# Thermostat.net
KiCad netlist of a schematic drawn in EAGLE
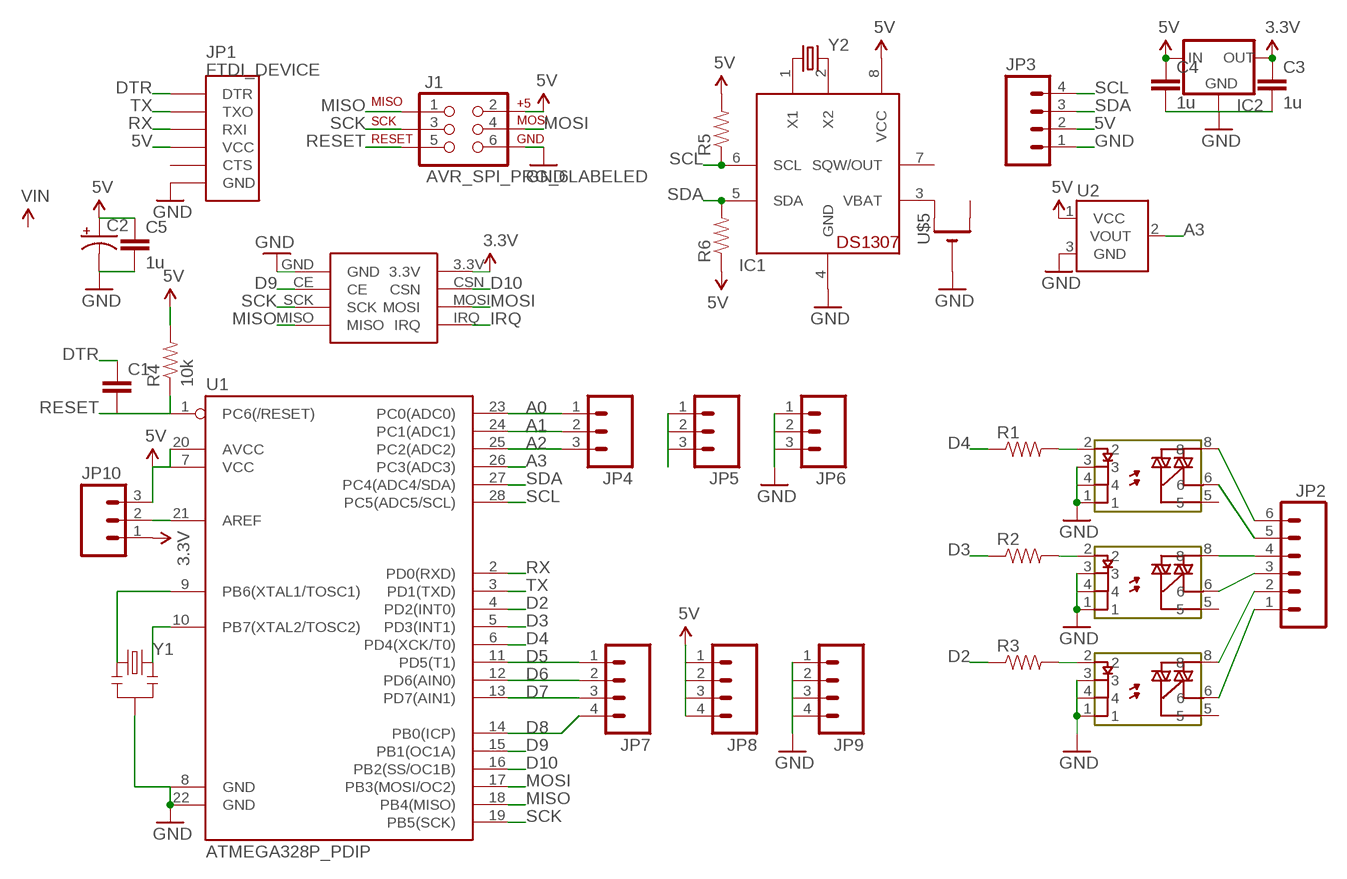
[diagram p0: schematic, sheet 1]

(export (version "E")
  (design (tool "Eeschema 10.0.6"))
  (components
    (comp (ref "C1")
      (value "CAPPTH")
      (footprint "eagle-import:CAP-PTH-SMALL")
      (libsource (lib "eagle-import") (part "CAPPTH"))
    )
    (comp (ref "C2")
      (value "CAP_POLPTH1")
      (footprint "eagle-import:CPOL-RADIAL-100UF-25V")
      (libsource (lib "eagle-import") (part "CAP_POLPTH1"))
    )
    (comp (ref "C3")
      (value "1u")
      (footprint "eagle-import:CAP-PTH-SMALL")
      (libsource (lib "eagle-import") (part "CAPPTH"))
    )
    (comp (ref "C4")
      (value "1u")
      (footprint "eagle-import:CAP-PTH-SMALL")
      (libsource (lib "eagle-import") (part "CAPPTH"))
    )
    (comp (ref "C5")
      (value "1u")
      (footprint "eagle-import:CAP-PTH-SMALL")
      (libsource (lib "eagle-import") (part "CAPPTH"))
    )
    (comp (ref "IC1")
      (value "DS1307")
      (footprint "eagle-import:DIL08")
      (libsource (lib "eagle-import") (part "DS1307"))
    )
    (comp (ref "IC2")
      (value "MCP1700INLINE")
      (footprint "eagle-import:TO92-INLINE")
      (libsource (lib "eagle-import") (part "MCP1700INLINE"))
    )
    (comp (ref "J1")
      (value "AVR_SPI_PRG_6LABELED")
      (footprint "eagle-import:2X3-NS")
      (libsource (lib "eagle-import") (part "AVR_SPI_PRG_6LABELED"))
    )
    (comp (ref "JP1")
      (value "FTDI_DEVICE")
      (footprint "eagle-import:FTDI_DEVICE_SIDE")
      (libsource (lib "eagle-import") (part "FTDI_DEVICE"))
    )
    (comp (ref "JP2")
      (value "M063.5MM-6")
      (footprint "eagle-import:SCREWTERMINAL-3.5MM-6")
      (libsource (lib "eagle-import") (part "M063.5MM-6"))
    )
    (comp (ref "JP3")
      (value "M04PTH")
      (footprint "eagle-import:1X04")
      (libsource (lib "eagle-import") (part "M04PTH"))
    )
    (comp (ref "JP4")
      (value "M03PTH")
      (footprint "eagle-import:1X03")
      (libsource (lib "eagle-import") (part "M03PTH"))
    )
    (comp (ref "JP5")
      (value "M03PTH")
      (footprint "eagle-import:1X03")
      (libsource (lib "eagle-import") (part "M03PTH"))
    )
    (comp (ref "JP6")
      (value "M03PTH")
      (footprint "eagle-import:1X03")
      (libsource (lib "eagle-import") (part "M03PTH"))
    )
    (comp (ref "JP7")
      (value "M04PTH")
      (footprint "eagle-import:1X04")
      (libsource (lib "eagle-import") (part "M04PTH"))
    )
    (comp (ref "JP8")
      (value "M04PTH")
      (footprint "eagle-import:1X04")
      (libsource (lib "eagle-import") (part "M04PTH"))
    )
    (comp (ref "JP9")
      (value "M04PTH")
      (footprint "eagle-import:1X04")
      (libsource (lib "eagle-import") (part "M04PTH"))
    )
    (comp (ref "JP10")
      (value "M03PTH")
      (footprint "eagle-import:1X03")
      (libsource (lib "eagle-import") (part "M03PTH"))
    )
    (comp (ref "R1")
      (value "RESISTORAXIAL-0.3")
      (footprint "eagle-import:AXIAL-0.3")
      (libsource (lib "eagle-import") (part "RESISTORAXIAL-0.3"))
    )
    (comp (ref "R2")
      (value "RESISTORAXIAL-0.3")
      (footprint "eagle-import:AXIAL-0.3")
      (libsource (lib "eagle-import") (part "RESISTORAXIAL-0.3"))
    )
    (comp (ref "R3")
      (value "RESISTORAXIAL-0.3")
      (footprint "eagle-import:AXIAL-0.3")
      (libsource (lib "eagle-import") (part "RESISTORAXIAL-0.3"))
    )
    (comp (ref "R4")
      (value "10k")
      (footprint "eagle-import:AXIAL-0.3")
      (libsource (lib "eagle-import") (part "RESISTORAXIAL-0.3"))
    )
    (comp (ref "R5")
      (value "RESISTORAXIAL-0.3")
      (footprint "eagle-import:AXIAL-0.3")
      (libsource (lib "eagle-import") (part "RESISTORAXIAL-0.3"))
    )
    (comp (ref "R6")
      (value "RESISTORAXIAL-0.3")
      (footprint "eagle-import:AXIAL-0.3")
      (libsource (lib "eagle-import") (part "RESISTORAXIAL-0.3"))
    )
    (comp (ref "U$1")
      (value "PR39MF5")
      (footprint "eagle-import:PR39MF51")
      (libsource (lib "eagle-import") (part "PR39MF5"))
    )
    (comp (ref "U$2")
      (value "PR39MF5")
      (footprint "eagle-import:PR39MF51")
      (libsource (lib "eagle-import") (part "PR39MF5"))
    )
    (comp (ref "U$3")
      (value "PR39MF5")
      (footprint "eagle-import:PR39MF51")
      (libsource (lib "eagle-import") (part "PR39MF5"))
    )
    (comp (ref "U$4")
      (value "RF24_MODULE")
      (footprint "eagle-import:RF24_SOCKET")
      (libsource (lib "eagle-import") (part "RF24_MODULE"))
    )
    (comp (ref "U$5")
      (value "CR1220THM")
      (footprint "eagle-import:CR1220-THM")
      (libsource (lib "eagle-import") (part "CR1220THM"))
    )
    (comp (ref "U1")
      (value "ATMEGA328P_PDIP")
      (footprint "eagle-import:DIL28-3")
      (libsource (lib "eagle-import") (part "ATMEGA328P_PDIP"))
    )
    (comp (ref "U2")
      (value "TMP36GT9")
      (footprint "eagle-import:TO-92")
      (libsource (lib "eagle-import") (part "TMP36GT9"))
    )
    (comp (ref "Y1")
      (value "RESONATORPTH")
      (footprint "eagle-import:RESONATOR-PTH")
      (libsource (lib "eagle-import") (part "RESONATORPTH"))
    )
    (comp (ref "Y2")
      (value "CRYSTALTC26H")
      (footprint "eagle-import:TC26H")
      (libsource (lib "eagle-import") (part "CRYSTALTC26H"))
    )
  )
  (nets
    (net (code "1") (name "/A0") (class "Default")
      (node (ref "JP4") (pin "1") (pinfunction "1_1") (pintype "passive"))
      (node (ref "U1") (pin "23") (pinfunction "PC0(ADC0)_23") (pintype "bidirectional"))
    )
    (net (code "2") (name "/A1") (class "Default")
      (node (ref "JP4") (pin "2") (pinfunction "2_2") (pintype "passive"))
      (node (ref "U1") (pin "24") (pinfunction "PC1(ADC1)_24") (pintype "bidirectional"))
    )
    (net (code "3") (name "/A2") (class "Default")
      (node (ref "JP4") (pin "3") (pinfunction "3_3") (pintype "passive"))
      (node (ref "U1") (pin "25") (pinfunction "PC2(ADC2)_25") (pintype "bidirectional"))
    )
    (net (code "4") (name "/A3") (class "Default")
      (node (ref "U1") (pin "26") (pinfunction "PC3(ADC3)_26") (pintype "bidirectional"))
      (node (ref "U2") (pin "2") (pinfunction "VOUT_2") (pintype "bidirectional"))
    )
    (net (code "5") (name "/AREF") (class "Default")
      (node (ref "JP10") (pin "2") (pinfunction "2_2") (pintype "passive"))
      (node (ref "JP5") (pin "1") (pinfunction "1_1") (pintype "passive"))
      (node (ref "JP5") (pin "2") (pinfunction "2_2") (pintype "passive"))
      (node (ref "JP5") (pin "3") (pinfunction "3_3") (pintype "passive"))
      (node (ref "U1") (pin "21") (pinfunction "AREF_21") (pintype "bidirectional"))
    )
    (net (code "6") (name "/D2") (class "Default")
      (node (ref "R3") (pin "P$1") (pinfunction "1_P$1") (pintype "passive"))
      (node (ref "U1") (pin "4") (pinfunction "PD2(INT0)_4") (pintype "bidirectional"))
    )
    (net (code "7") (name "/D3") (class "Default")
      (node (ref "R2") (pin "P$1") (pinfunction "1_P$1") (pintype "passive"))
      (node (ref "U1") (pin "5") (pinfunction "PD3(INT1)_5") (pintype "bidirectional"))
    )
    (net (code "8") (name "/D4") (class "Default")
      (node (ref "R1") (pin "P$1") (pinfunction "1_P$1") (pintype "passive"))
      (node (ref "U1") (pin "6") (pinfunction "PD4(XCK/T0)_6") (pintype "bidirectional"))
    )
    (net (code "9") (name "/D5") (class "Default")
      (node (ref "JP7") (pin "1") (pinfunction "1_1") (pintype "passive"))
      (node (ref "U1") (pin "11") (pinfunction "PD5(T1)_11") (pintype "bidirectional"))
    )
    (net (code "10") (name "/D6") (class "Default")
      (node (ref "JP7") (pin "2") (pinfunction "2_2") (pintype "passive"))
      (node (ref "U1") (pin "12") (pinfunction "PD6(AIN0)_12") (pintype "bidirectional"))
    )
    (net (code "11") (name "/D7") (class "Default")
      (node (ref "JP7") (pin "3") (pinfunction "3_3") (pintype "passive"))
      (node (ref "U1") (pin "13") (pinfunction "PD7(AIN1)_13") (pintype "bidirectional"))
    )
    (net (code "12") (name "/D8") (class "Default")
      (node (ref "JP7") (pin "4") (pinfunction "4_4") (pintype "passive"))
      (node (ref "U1") (pin "14") (pinfunction "PB0(ICP)_14") (pintype "bidirectional"))
    )
    (net (code "13") (name "/D9") (class "Default")
      (node (ref "U$4") (pin "CE") (pinfunction "CE_CE") (pintype "bidirectional"))
      (node (ref "U1") (pin "15") (pinfunction "PB1(OC1A)_15") (pintype "bidirectional"))
    )
    (net (code "14") (name "/D10") (class "Default")
      (node (ref "U$4") (pin "CSN") (pinfunction "CSN_CSN") (pintype "bidirectional"))
      (node (ref "U1") (pin "16") (pinfunction "PB2(SS/OC1B)_16") (pintype "bidirectional"))
    )
    (net (code "15") (name "/DTR") (class "Default")
      (node (ref "C1") (pin "1") (pinfunction "1_1") (pintype "passive"))
      (node (ref "JP1") (pin "P$1") (pinfunction "DTR_P$1") (pintype "bidirectional"))
    )
    (net (code "16") (name "/IRQ") (class "Default")
      (node (ref "U$4") (pin "IRQ") (pinfunction "IRQ_IRQ") (pintype "bidirectional"))
    )
    (net (code "17") (name "/MISO") (class "Default")
      (node (ref "J1") (pin "1") (pinfunction "1_1") (pintype "passive"))
      (node (ref "U$4") (pin "MISO") (pinfunction "MISO_MISO") (pintype "bidirectional"))
      (node (ref "U1") (pin "18") (pinfunction "PB4(MISO)_18") (pintype "bidirectional"))
    )
    (net (code "18") (name "/MOSI") (class "Default")
      (node (ref "J1") (pin "4") (pinfunction "4_4") (pintype "passive"))
      (node (ref "U$4") (pin "MOSI") (pinfunction "MOSI_MOSI") (pintype "bidirectional"))
      (node (ref "U1") (pin "17") (pinfunction "PB3(MOSI/OC2)_17") (pintype "bidirectional"))
    )
    (net (code "19") (name "/RESET") (class "Default")
      (node (ref "C1") (pin "2") (pinfunction "2_2") (pintype "passive"))
      (node (ref "J1") (pin "5") (pinfunction "5_5") (pintype "passive"))
      (node (ref "R4") (pin "P$1") (pinfunction "1_P$1") (pintype "passive"))
      (node (ref "U1") (pin "1") (pinfunction "PC6(/RESET)_1") (pintype "bidirectional"))
    )
    (net (code "20") (name "/RX") (class "Default")
      (node (ref "JP1") (pin "P$3") (pinfunction "RXI_P$3") (pintype "bidirectional"))
      (node (ref "U1") (pin "2") (pinfunction "PD0(RXD)_2") (pintype "bidirectional"))
    )
    (net (code "21") (name "/SCK") (class "Default")
      (node (ref "J1") (pin "3") (pinfunction "3_3") (pintype "passive"))
      (node (ref "U$4") (pin "SCK") (pinfunction "SCK_SCK") (pintype "bidirectional"))
      (node (ref "U1") (pin "19") (pinfunction "PB5(SCK)_19") (pintype "bidirectional"))
    )
    (net (code "22") (name "/SCL") (class "Default")
      (node (ref "IC1") (pin "6") (pinfunction "SCL_6") (pintype "bidirectional"))
      (node (ref "JP3") (pin "4") (pinfunction "4_4") (pintype "passive"))
      (node (ref "R5") (pin "P$1") (pinfunction "1_P$1") (pintype "passive"))
      (node (ref "U1") (pin "28") (pinfunction "PC5(ADC5/SCL)_28") (pintype "bidirectional"))
    )
    (net (code "23") (name "/SDA") (class "Default")
      (node (ref "IC1") (pin "5") (pinfunction "SDA_5") (pintype "bidirectional"))
      (node (ref "JP3") (pin "3") (pinfunction "3_3") (pintype "passive"))
      (node (ref "R6") (pin "P$2") (pinfunction "2_P$2") (pintype "passive"))
      (node (ref "U1") (pin "27") (pinfunction "PC4(ADC4/SDA)_27") (pintype "bidirectional"))
    )
    (net (code "24") (name "/TX") (class "Default")
      (node (ref "JP1") (pin "P$2") (pinfunction "TXO_P$2") (pintype "bidirectional"))
      (node (ref "U1") (pin "3") (pinfunction "PD1(TXD)_3") (pintype "bidirectional"))
    )
    (net (code "25") (name "3.3V") (class "Default")
      (node (ref "C3") (pin "1") (pinfunction "1_1") (pintype "passive"))
      (node (ref "IC2") (pin "3") (pinfunction "OUT_3") (pintype "passive"))
      (node (ref "JP10") (pin "1") (pinfunction "1_1") (pintype "passive"))
      (node (ref "U$4") (pin "3.3V") (pinfunction "3.3V_3.3V") (pintype "bidirectional"))
    )
    (net (code "26") (name "5V") (class "Default")
      (node (ref "C2") (pin "1") (pinfunction "+_1") (pintype "passive"))
      (node (ref "C4") (pin "1") (pinfunction "1_1") (pintype "passive"))
      (node (ref "C5") (pin "1") (pinfunction "1_1") (pintype "passive"))
      (node (ref "IC1") (pin "8") (pinfunction "VCC_8") (pintype "power_in"))
      (node (ref "IC2") (pin "2") (pinfunction "IN_2") (pintype "input"))
      (node (ref "J1") (pin "2") (pinfunction "2_2") (pintype "passive"))
      (node (ref "JP1") (pin "P$4") (pinfunction "VCC_P$4") (pintype "bidirectional"))
      (node (ref "JP10") (pin "3") (pinfunction "3_3") (pintype "passive"))
      (node (ref "JP3") (pin "2") (pinfunction "2_2") (pintype "passive"))
      (node (ref "JP8") (pin "1") (pinfunction "1_1") (pintype "passive"))
      (node (ref "JP8") (pin "2") (pinfunction "2_2") (pintype "passive"))
      (node (ref "JP8") (pin "3") (pinfunction "3_3") (pintype "passive"))
      (node (ref "JP8") (pin "4") (pinfunction "4_4") (pintype "passive"))
      (node (ref "R4") (pin "P$2") (pinfunction "2_P$2") (pintype "passive"))
      (node (ref "R5") (pin "P$2") (pinfunction "2_P$2") (pintype "passive"))
      (node (ref "R6") (pin "P$1") (pinfunction "1_P$1") (pintype "passive"))
      (node (ref "U1") (pin "20") (pinfunction "AVCC_20") (pintype "bidirectional"))
      (node (ref "U1") (pin "7") (pinfunction "VCC_7") (pintype "bidirectional"))
      (node (ref "U2") (pin "1") (pinfunction "VCC_1") (pintype "bidirectional"))
    )
    (net (code "27") (name "GND") (class "Default")
      (node (ref "C2") (pin "2") (pinfunction "-_2") (pintype "passive"))
      (node (ref "C3") (pin "2") (pinfunction "2_2") (pintype "passive"))
      (node (ref "C4") (pin "2") (pinfunction "2_2") (pintype "passive"))
      (node (ref "C5") (pin "2") (pinfunction "2_2") (pintype "passive"))
      (node (ref "IC1") (pin "4") (pinfunction "GND_4") (pintype "power_in"))
      (node (ref "IC2") (pin "1") (pinfunction "GND_1") (pintype "input"))
      (node (ref "J1") (pin "6") (pinfunction "6_6") (pintype "passive"))
      (node (ref "JP1") (pin "P$6") (pinfunction "GND_P$6") (pintype "bidirectional"))
      (node (ref "JP3") (pin "1") (pinfunction "1_1") (pintype "passive"))
      (node (ref "JP6") (pin "1") (pinfunction "1_1") (pintype "passive"))
      (node (ref "JP6") (pin "2") (pinfunction "2_2") (pintype "passive"))
      (node (ref "JP6") (pin "3") (pinfunction "3_3") (pintype "passive"))
      (node (ref "JP9") (pin "1") (pinfunction "1_1") (pintype "passive"))
      (node (ref "JP9") (pin "2") (pinfunction "2_2") (pintype "passive"))
      (node (ref "JP9") (pin "3") (pinfunction "3_3") (pintype "passive"))
      (node (ref "JP9") (pin "4") (pinfunction "4_4") (pintype "passive"))
      (node (ref "U$1") (pin "1") (pinfunction "1_1") (pintype "input"))
      (node (ref "U$1") (pin "3") (pinfunction "3_3") (pintype "input"))
      (node (ref "U$1") (pin "4") (pinfunction "4_4") (pintype "input"))
      (node (ref "U$2") (pin "1") (pinfunction "1_1") (pintype "input"))
      (node (ref "U$2") (pin "3") (pinfunction "3_3") (pintype "input"))
      (node (ref "U$2") (pin "4") (pinfunction "4_4") (pintype "input"))
      (node (ref "U$3") (pin "1") (pinfunction "1_1") (pintype "input"))
      (node (ref "U$3") (pin "3") (pinfunction "3_3") (pintype "input"))
      (node (ref "U$3") (pin "4") (pinfunction "4_4") (pintype "input"))
      (node (ref "U$4") (pin "GND") (pinfunction "GND_GND") (pintype "bidirectional"))
      (node (ref "U$5") (pin "-") (pinfunction "-_-") (pintype "passive"))
      (node (ref "U1") (pin "22") (pinfunction "GND_22") (pintype "bidirectional"))
      (node (ref "U1") (pin "8") (pinfunction "GND_8") (pintype "bidirectional"))
      (node (ref "U2") (pin "3") (pinfunction "GND_3") (pintype "bidirectional"))
      (node (ref "Y1") (pin "2") (pinfunction "2_2") (pintype "passive"))
    )
    (net (code "28") (name "Net-(IC1-VBAT)") (class "Default")
      (node (ref "IC1") (pin "3") (pinfunction "VBAT_3") (pintype "power_in"))
      (node (ref "U$5") (pin "+1") (pinfunction "+_+1") (pintype "passive"))
    )
    (net (code "29") (name "Net-(IC1-X1)") (class "Default")
      (node (ref "IC1") (pin "1") (pinfunction "X1_1") (pintype "passive"))
      (node (ref "Y2") (pin "1") (pinfunction "1_1") (pintype "passive"))
    )
    (net (code "30") (name "Net-(IC1-X2)") (class "Default")
      (node (ref "IC1") (pin "2") (pinfunction "X2_2") (pintype "passive"))
      (node (ref "Y2") (pin "2") (pinfunction "2_2") (pintype "passive"))
    )
    (net (code "31") (name "Net-(JP2-Pad1)") (class "Default")
      (node (ref "JP2") (pin "1") (pinfunction "1_1") (pintype "passive"))
      (node (ref "U$3") (pin "6") (pinfunction "6_6") (pintype "output"))
    )
    (net (code "32") (name "Net-(JP2-Pad2)") (class "Default")
      (node (ref "JP2") (pin "2") (pinfunction "2_2") (pintype "passive"))
      (node (ref "U$3") (pin "8") (pinfunction "8_8") (pintype "output"))
    )
    (net (code "33") (name "Net-(JP2-Pad3)") (class "Default")
      (node (ref "JP2") (pin "3") (pinfunction "3_3") (pintype "passive"))
      (node (ref "U$2") (pin "6") (pinfunction "6_6") (pintype "output"))
    )
    (net (code "34") (name "Net-(JP2-Pad4)") (class "Default")
      (node (ref "JP2") (pin "4") (pinfunction "4_4") (pintype "passive"))
      (node (ref "U$2") (pin "8") (pinfunction "8_8") (pintype "output"))
    )
    (net (code "35") (name "Net-(JP2-Pad5)") (class "Default")
      (node (ref "JP2") (pin "5") (pinfunction "5_5") (pintype "passive"))
      (node (ref "U$1") (pin "6") (pinfunction "6_6") (pintype "output"))
    )
    (net (code "36") (name "Net-(JP2-Pad6)") (class "Default")
      (node (ref "JP2") (pin "6") (pinfunction "6_6") (pintype "passive"))
      (node (ref "U$1") (pin "8") (pinfunction "8_8") (pintype "output"))
    )
    (net (code "37") (name "Net-(R1-2)") (class "Default")
      (node (ref "R1") (pin "P$2") (pinfunction "2_P$2") (pintype "passive"))
      (node (ref "U$1") (pin "2") (pinfunction "2_2") (pintype "input"))
    )
    (net (code "38") (name "Net-(R2-2)") (class "Default")
      (node (ref "R2") (pin "P$2") (pinfunction "2_P$2") (pintype "passive"))
      (node (ref "U$2") (pin "2") (pinfunction "2_2") (pintype "input"))
    )
    (net (code "39") (name "Net-(R3-2)") (class "Default")
      (node (ref "R3") (pin "P$2") (pinfunction "2_P$2") (pintype "passive"))
      (node (ref "U$3") (pin "2") (pinfunction "2_2") (pintype "input"))
    )
    (net (code "40") (name "Net-(U1-PB6(XTAL1{slash}TOSC1))") (class "Default")
      (node (ref "U1") (pin "9") (pinfunction "PB6(XTAL1/TOSC1)_9") (pintype "bidirectional"))
      (node (ref "Y1") (pin "1") (pinfunction "1_1") (pintype "passive"))
    )
    (net (code "41") (name "Net-(U1-PB7(XTAL2{slash}TOSC2))") (class "Default")
      (node (ref "U1") (pin "10") (pinfunction "PB7(XTAL2/TOSC2)_10") (pintype "bidirectional"))
      (node (ref "Y1") (pin "3") (pinfunction "3_3") (pintype "passive"))
    )
    (net (code "43") (name "unconnected-(IC1-SQW{slash}OUT-Pad7)") (class "Default")
      (node (ref "IC1") (pin "7") (pinfunction "SQW/OUT_7") (pintype "bidirectional"))
    )
    (net (code "44") (name "unconnected-(JP1-CTS-PadP$5)") (class "Default")
      (node (ref "JP1") (pin "P$5") (pinfunction "CTS_P$5") (pintype "bidirectional"))
    )
    (net (code "45") (name "unconnected-(U$1-Pad5)") (class "Default")
      (node (ref "U$1") (pin "5") (pinfunction "5_5") (pintype "no_connect"))
    )
    (net (code "46") (name "unconnected-(U$2-Pad5)") (class "Default")
      (node (ref "U$2") (pin "5") (pinfunction "5_5") (pintype "no_connect"))
    )
    (net (code "47") (name "unconnected-(U$3-Pad5)") (class "Default")
      (node (ref "U$3") (pin "5") (pinfunction "5_5") (pintype "no_connect"))
    )
    (net (code "48") (name "unconnected-(U$5-+1-Pad+2)") (class "Default")
      (node (ref "U$5") (pin "+2") (pinfunction "+1_+2") (pintype "passive"))
    )
  )
)
